# DiscoveryConnector_V1_1.net
KiCad netlist of a schematic drawn in EAGLE
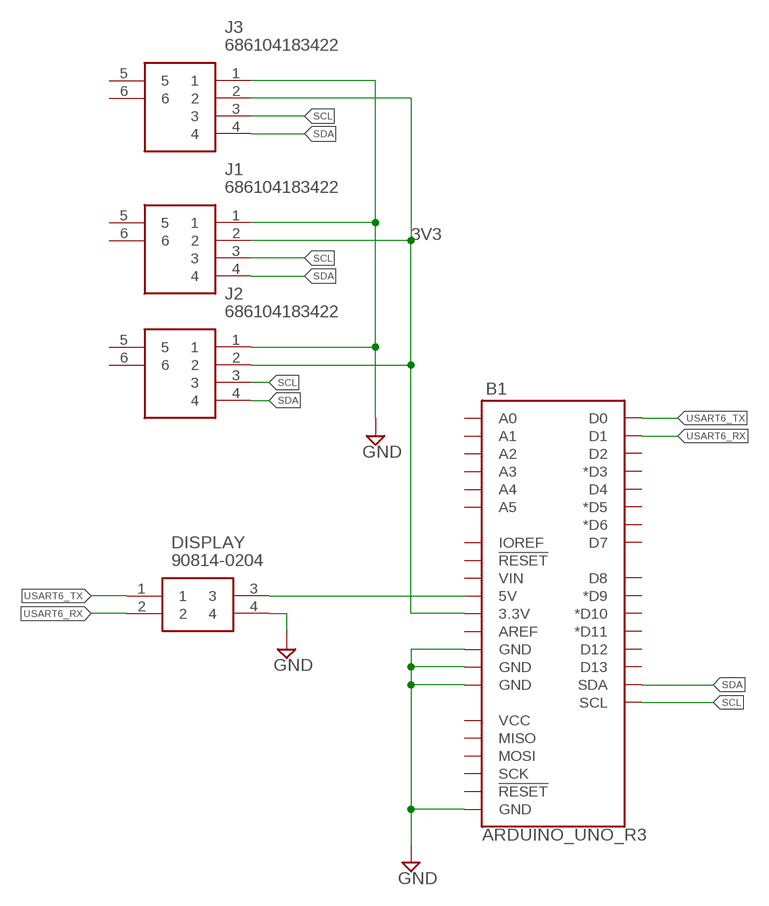
[diagram p0: schematic, sheet 1]

(export (version "E")
  (design (tool "Eeschema 10.0.6"))
  (components
    (comp (ref "B1")
      (value "ARDUINO_UNO_R3")
      (footprint "eagle-import:ARDUINO_R3")
      (libsource (lib "eagle-import") (part "ARDUINO_UNO_R3"))
    )
    (comp (ref "DISPLAY")
      (value "90814-0204")
      (footprint "eagle-import:MOLEX_90814-0204")
      (fields (field (name "MOUSER_PART_NUMBER") "538-90814-0204"))
      (libsource (lib "eagle-import") (part "90814-0204"))
    )
    (comp (ref "J1")
      (value "686104183422")
      (footprint "eagle-import:686104183422")
      (fields (field (name "MOUSER_PART_NUMBER") "710-686104183422"))
      (libsource (lib "eagle-import") (part "686104183422"))
    )
    (comp (ref "J2")
      (value "686104183422")
      (footprint "eagle-import:686104183422")
      (fields (field (name "MOUSER_PART_NUMBER") "710-686104183422"))
      (libsource (lib "eagle-import") (part "686104183422"))
    )
    (comp (ref "J3")
      (value "686104183422")
      (footprint "eagle-import:686104183422")
      (fields (field (name "MOUSER_PART_NUMBER") "710-686104183422"))
      (libsource (lib "eagle-import") (part "686104183422"))
    )
  )
  (nets
    (net (code "1") (name "/3V3") (class "Default")
      (node (ref "B1") (pin "3.3V") (pinfunction "3.3V_3.3V") (pintype "bidirectional"))
      (node (ref "J1") (pin "2") (pinfunction "2_2") (pintype "bidirectional"))
      (node (ref "J2") (pin "2") (pinfunction "2_2") (pintype "bidirectional"))
      (node (ref "J3") (pin "2") (pinfunction "2_2") (pintype "bidirectional"))
    )
    (net (code "2") (name "GND") (class "Default")
      (node (ref "B1") (pin "GND@1") (pinfunction "GND_GND@1") (pintype "bidirectional"))
      (node (ref "B1") (pin "GND@2") (pinfunction "GND_GND@2") (pintype "bidirectional"))
      (node (ref "B1") (pin "GND@3") (pinfunction "GND_GND@3") (pintype "bidirectional"))
      (node (ref "B1") (pin "GND@4") (pinfunction "GND_GND@4") (pintype "bidirectional"))
      (node (ref "DISPLAY") (pin "4") (pinfunction "4_4") (pintype "bidirectional"))
      (node (ref "J1") (pin "1") (pinfunction "1_1") (pintype "bidirectional"))
      (node (ref "J2") (pin "1") (pinfunction "1_1") (pintype "bidirectional"))
      (node (ref "J3") (pin "1") (pinfunction "1_1") (pintype "bidirectional"))
    )
    (net (code "3") (name "Net-(B1-Pad5V)") (class "Default")
      (node (ref "B1") (pin "5V") (pinfunction "5V_5V") (pintype "bidirectional"))
      (node (ref "DISPLAY") (pin "3") (pinfunction "3_3") (pintype "bidirectional"))
    )
    (net (code "4") (name "SCL") (class "Default")
      (node (ref "B1") (pin "SCL") (pinfunction "SCL_SCL") (pintype "bidirectional"))
      (node (ref "J1") (pin "3") (pinfunction "3_3") (pintype "bidirectional"))
      (node (ref "J2") (pin "3") (pinfunction "3_3") (pintype "bidirectional"))
      (node (ref "J3") (pin "3") (pinfunction "3_3") (pintype "bidirectional"))
    )
    (net (code "5") (name "SDA") (class "Default")
      (node (ref "B1") (pin "SDA") (pinfunction "SDA_SDA") (pintype "bidirectional"))
      (node (ref "J1") (pin "4") (pinfunction "4_4") (pintype "bidirectional"))
      (node (ref "J2") (pin "4") (pinfunction "4_4") (pintype "bidirectional"))
      (node (ref "J3") (pin "4") (pinfunction "4_4") (pintype "bidirectional"))
    )
    (net (code "6") (name "USART6_RX") (class "Default")
      (node (ref "B1") (pin "D1") (pinfunction "D1_D1") (pintype "bidirectional"))
      (node (ref "DISPLAY") (pin "2") (pinfunction "2_2") (pintype "bidirectional"))
    )
    (net (code "7") (name "USART6_TX") (class "Default")
      (node (ref "B1") (pin "D0") (pinfunction "D0_D0") (pintype "bidirectional"))
      (node (ref "DISPLAY") (pin "1") (pinfunction "1_1") (pintype "bidirectional"))
    )
    (net (code "8") (name "unconnected-(B1-*D3-PadD3)") (class "Default")
      (node (ref "B1") (pin "D3") (pinfunction "*D3_D3") (pintype "bidirectional"))
    )
    (net (code "9") (name "unconnected-(B1-*D5-PadD5)") (class "Default")
      (node (ref "B1") (pin "D5") (pinfunction "*D5_D5") (pintype "bidirectional"))
    )
    (net (code "10") (name "unconnected-(B1-*D6-PadD6)") (class "Default")
      (node (ref "B1") (pin "D6") (pinfunction "*D6_D6") (pintype "bidirectional"))
    )
    (net (code "11") (name "unconnected-(B1-*D9-PadD9)") (class "Default")
      (node (ref "B1") (pin "D9") (pinfunction "*D9_D9") (pintype "bidirectional"))
    )
    (net (code "12") (name "unconnected-(B1-*D10-PadD10)") (class "Default")
      (node (ref "B1") (pin "D10") (pinfunction "*D10_D10") (pintype "bidirectional"))
    )
    (net (code "13") (name "unconnected-(B1-*D11-PadD11)") (class "Default")
      (node (ref "B1") (pin "D11") (pinfunction "*D11_D11") (pintype "bidirectional"))
    )
    (net (code "14") (name "unconnected-(B1-PadA0)") (class "Default")
      (node (ref "B1") (pin "A0") (pinfunction "A0_A0") (pintype "bidirectional"))
    )
    (net (code "15") (name "unconnected-(B1-PadA1)") (class "Default")
      (node (ref "B1") (pin "A1") (pinfunction "A1_A1") (pintype "bidirectional"))
    )
    (net (code "16") (name "unconnected-(B1-PadA2)") (class "Default")
      (node (ref "B1") (pin "A2") (pinfunction "A2_A2") (pintype "bidirectional"))
    )
    (net (code "17") (name "unconnected-(B1-PadA3)") (class "Default")
      (node (ref "B1") (pin "A3") (pinfunction "A3_A3") (pintype "bidirectional"))
    )
    (net (code "18") (name "unconnected-(B1-PadA4)") (class "Default")
      (node (ref "B1") (pin "A4") (pinfunction "A4_A4") (pintype "bidirectional"))
    )
    (net (code "19") (name "unconnected-(B1-PadA5)") (class "Default")
      (node (ref "B1") (pin "A5") (pinfunction "A5_A5") (pintype "bidirectional"))
    )
    (net (code "20") (name "unconnected-(B1-PadAREF)") (class "Default")
      (node (ref "B1") (pin "AREF") (pinfunction "AREF_AREF") (pintype "bidirectional"))
    )
    (net (code "21") (name "unconnected-(B1-PadD2)") (class "Default")
      (node (ref "B1") (pin "D2") (pinfunction "D2_D2") (pintype "bidirectional"))
    )
    (net (code "22") (name "unconnected-(B1-PadD4)") (class "Default")
      (node (ref "B1") (pin "D4") (pinfunction "D4_D4") (pintype "bidirectional"))
    )
    (net (code "23") (name "unconnected-(B1-PadD7)") (class "Default")
      (node (ref "B1") (pin "D7") (pinfunction "D7_D7") (pintype "bidirectional"))
    )
    (net (code "24") (name "unconnected-(B1-PadD8)") (class "Default")
      (node (ref "B1") (pin "D8") (pinfunction "D8_D8") (pintype "bidirectional"))
    )
    (net (code "25") (name "unconnected-(B1-PadD12)") (class "Default")
      (node (ref "B1") (pin "D12") (pinfunction "D12_D12") (pintype "bidirectional"))
    )
    (net (code "26") (name "unconnected-(B1-PadD13)") (class "Default")
      (node (ref "B1") (pin "D13") (pinfunction "D13_D13") (pintype "bidirectional"))
    )
    (net (code "27") (name "unconnected-(B1-PadIOREF)") (class "Default")
      (node (ref "B1") (pin "IOREF") (pinfunction "IOREF_IOREF") (pintype "bidirectional"))
    )
    (net (code "28") (name "unconnected-(B1-PadMISO)") (class "Default")
      (node (ref "B1") (pin "MISO") (pinfunction "MISO_MISO") (pintype "bidirectional"))
    )
    (net (code "29") (name "unconnected-(B1-PadMOSI)") (class "Default")
      (node (ref "B1") (pin "MOSI") (pinfunction "MOSI_MOSI") (pintype "bidirectional"))
    )
    (net (code "30") (name "unconnected-(B1-PadSCK)") (class "Default")
      (node (ref "B1") (pin "SCK") (pinfunction "SCK_SCK") (pintype "bidirectional"))
    )
    (net (code "31") (name "unconnected-(B1-PadVCC)") (class "Default")
      (node (ref "B1") (pin "VCC") (pinfunction "VCC_VCC") (pintype "bidirectional"))
    )
    (net (code "32") (name "unconnected-(B1-PadVIN)") (class "Default")
      (node (ref "B1") (pin "VIN") (pinfunction "VIN_VIN") (pintype "bidirectional"))
    )
    (net (code "33") (name "unconnected-(B1-~{RESET}-PadRESET@1)") (class "Default")
      (node (ref "B1") (pin "RESET@1") (pinfunction "~{RESET}_RESET@1") (pintype "bidirectional"))
    )
    (net (code "34") (name "unconnected-(B1-~{RESET}-PadRESET@2)") (class "Default")
      (node (ref "B1") (pin "RESET@2") (pinfunction "~{RESET}_RESET@2") (pintype "bidirectional"))
    )
    (net (code "35") (name "unconnected-(J1-Pad5)") (class "Default")
      (node (ref "J1") (pin "5") (pinfunction "5_5") (pintype "bidirectional"))
    )
    (net (code "36") (name "unconnected-(J1-Pad6)") (class "Default")
      (node (ref "J1") (pin "6") (pinfunction "6_6") (pintype "bidirectional"))
    )
    (net (code "37") (name "unconnected-(J2-Pad5)") (class "Default")
      (node (ref "J2") (pin "5") (pinfunction "5_5") (pintype "bidirectional"))
    )
    (net (code "38") (name "unconnected-(J2-Pad6)") (class "Default")
      (node (ref "J2") (pin "6") (pinfunction "6_6") (pintype "bidirectional"))
    )
    (net (code "39") (name "unconnected-(J3-Pad5)") (class "Default")
      (node (ref "J3") (pin "5") (pinfunction "5_5") (pintype "bidirectional"))
    )
    (net (code "40") (name "unconnected-(J3-Pad6)") (class "Default")
      (node (ref "J3") (pin "6") (pinfunction "6_6") (pintype "bidirectional"))
    )
  )
)
